# little2wire.net
KiCad netlist of a schematic drawn in EAGLE
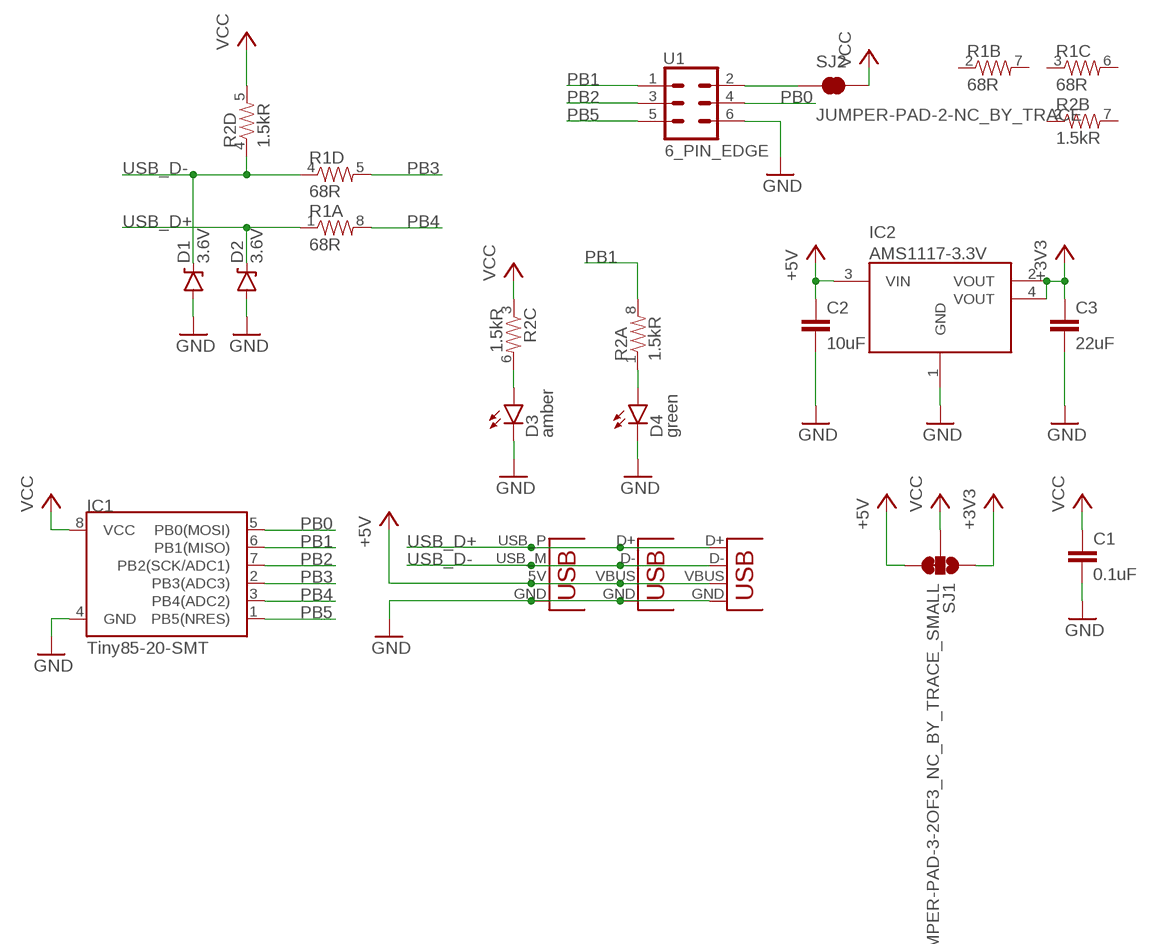
[diagram p0: schematic, sheet 1]

(export (version "E")
  (design (tool "Eeschema 10.0.6"))
  (components
    (comp (ref "C1")
      (value "0.1uF")
      (footprint "eagle-import:0805")
      (libsource (lib "eagle-import") (part "CAPACITOR0805"))
    )
    (comp (ref "C2")
      (value "10uF")
      (footprint "eagle-import:0805")
      (libsource (lib "eagle-import") (part "CAPACITOR0805"))
    )
    (comp (ref "C3")
      (value "22uF")
      (footprint "eagle-import:0805")
      (libsource (lib "eagle-import") (part "CAPACITOR0805"))
    )
    (comp (ref "D1")
      (value "3.6V")
      (footprint "eagle-import:SOD-323")
      (libsource (lib "eagle-import") (part "DIODE-ZENER_SOD323"))
    )
    (comp (ref "D2")
      (value "3.6V")
      (footprint "eagle-import:SOD-323")
      (libsource (lib "eagle-import") (part "DIODE-ZENER_SOD323"))
    )
    (comp (ref "D3")
      (value "amber")
      (footprint "eagle-import:LED-805")
      (libsource (lib "eagle-import") (part "LED805"))
    )
    (comp (ref "D4")
      (value "green")
      (footprint "eagle-import:LED-805")
      (libsource (lib "eagle-import") (part "LED805"))
    )
    (comp (ref "IC1")
      (value "Tiny85-20-SMT")
      (footprint "eagle-import:SO08-EIAJ")
      (libsource (lib "eagle-import") (part "ATTINY45TINY85-20-SMT"))
    )
    (comp (ref "IC2")
      (value "AMS1117-3.3V")
      (footprint "eagle-import:SOT223")
      (libsource (lib "eagle-import") (part "AMS1117_SOT223"))
    )
    (comp (ref "JP1")
      (value "USBPCB")
      (footprint "eagle-import:USB-A-PCB")
      (libsource (lib "eagle-import") (part "USBPCB"))
    )
    (comp (ref "JP2")
      (value "USBSMD")
      (footprint "eagle-import:USB-MINIB")
      (libsource (lib "eagle-import") (part "USBSMD"))
    )
    (comp (ref "JP3")
      (value "USB-MICROB")
      (footprint "eagle-import:USB-MICROB")
      (libsource (lib "eagle-import") (part "USB-MICROB"))
    )
    (comp (ref "R1")
      (value "68R")
      (footprint "eagle-import:1206-ARRAY")
      (libsource (lib "eagle-import") (part "RESISTOR-ARRAY1206ARR"))
    )
    (comp (ref "R2")
      (value "1.5kR")
      (footprint "eagle-import:1206-ARRAY")
      (libsource (lib "eagle-import") (part "RESISTOR-ARRAY1206ARR"))
    )
    (comp (ref "SJ1")
      (value "JUMPER-PAD-3-2OF3_NC_BY_TRACE_SMALL")
      (footprint "eagle-import:PAD-JUMPER-3-2OF3_NC_BY_TRACE_YES_SILK_FULL_BOX")
      (libsource (lib "eagle-import") (part "JUMPER-PAD-3-2OF3_NC_BY_TRACE_SMALL"))
    )
    (comp (ref "SJ2")
      (value "JUMPER-PAD-2-NC_BY_TRACE")
      (footprint "eagle-import:PAD-JUMPER-2-NC_BY_TRACE_YES_SILK")
      (libsource (lib "eagle-import") (part "JUMPER-PAD-2-NC_BY_TRACE"))
    )
    (comp (ref "U1")
      (value "6_PIN_EDGE")
      (footprint "eagle-import:6_PIN_EDGE")
      (libsource (lib "eagle-import") (part "6_PIN_EDGE"))
    )
  )
  (nets
    (net (code "1") (name "+3V3") (class "Default")
      (node (ref "C3") (pin "1") (pinfunction "1_1") (pintype "passive"))
      (node (ref "IC2") (pin "2") (pinfunction "VOUT_2") (pintype "bidirectional"))
      (node (ref "IC2") (pin "4") (pinfunction "VOUT_4") (pintype "bidirectional"))
      (node (ref "SJ1") (pin "1") (pinfunction "1_1") (pintype "passive"))
    )
    (net (code "2") (name "+5V") (class "Default")
      (node (ref "C2") (pin "1") (pinfunction "1_1") (pintype "passive"))
      (node (ref "IC2") (pin "3") (pinfunction "VIN_3") (pintype "bidirectional"))
      (node (ref "JP1") (pin "5V") (pinfunction "VBUS_5V") (pintype "bidirectional"))
      (node (ref "JP2") (pin "VBUS") (pinfunction "VBUS_VBUS") (pintype "bidirectional"))
      (node (ref "JP3") (pin "VBUS") (pinfunction "VBUS_VBUS") (pintype "bidirectional"))
      (node (ref "SJ1") (pin "3") (pinfunction "3_3") (pintype "passive"))
    )
    (net (code "3") (name "/PB0") (class "Default")
      (node (ref "IC1") (pin "5") (pinfunction "PB0(MOSI)_5") (pintype "bidirectional"))
      (node (ref "U1") (pin "4") (pinfunction "4_4") (pintype "passive"))
    )
    (net (code "4") (name "/PB1") (class "Default")
      (node (ref "IC1") (pin "6") (pinfunction "PB1(MISO)_6") (pintype "bidirectional"))
      (node (ref "R2") (pin "8") (pinfunction "2_8") (pintype "passive"))
      (node (ref "U1") (pin "1") (pinfunction "1_1") (pintype "passive"))
    )
    (net (code "5") (name "/PB2") (class "Default")
      (node (ref "IC1") (pin "7") (pinfunction "PB2(SCK/ADC1)_7") (pintype "bidirectional"))
      (node (ref "U1") (pin "3") (pinfunction "3_3") (pintype "passive"))
    )
    (net (code "6") (name "/PB3") (class "Default")
      (node (ref "IC1") (pin "2") (pinfunction "PB3(ADC3)_2") (pintype "bidirectional"))
      (node (ref "R1") (pin "5") (pinfunction "2_5") (pintype "passive"))
    )
    (net (code "7") (name "/PB4") (class "Default")
      (node (ref "IC1") (pin "3") (pinfunction "PB4(ADC2)_3") (pintype "bidirectional"))
      (node (ref "R1") (pin "8") (pinfunction "2_8") (pintype "passive"))
    )
    (net (code "8") (name "/PB5") (class "Default")
      (node (ref "IC1") (pin "1") (pinfunction "PB5(NRES)_1") (pintype "bidirectional"))
      (node (ref "U1") (pin "5") (pinfunction "5_5") (pintype "passive"))
    )
    (net (code "9") (name "/USB_D+") (class "Default")
      (node (ref "D2") (pin "C") (pinfunction "C_C") (pintype "passive"))
      (node (ref "JP1") (pin "USB_P") (pinfunction "D+_USB_P") (pintype "bidirectional"))
      (node (ref "JP2") (pin "D+") (pinfunction "D+_D+") (pintype "bidirectional"))
      (node (ref "JP3") (pin "D+") (pinfunction "D+_D+") (pintype "bidirectional"))
      (node (ref "R1") (pin "1") (pinfunction "1_1") (pintype "passive"))
    )
    (net (code "10") (name "/USB_D-") (class "Default")
      (node (ref "D1") (pin "C") (pinfunction "C_C") (pintype "passive"))
      (node (ref "JP1") (pin "USB_M") (pinfunction "D-_USB_M") (pintype "bidirectional"))
      (node (ref "JP2") (pin "D-") (pinfunction "D-_D-") (pintype "bidirectional"))
      (node (ref "JP3") (pin "D-") (pinfunction "D-_D-") (pintype "bidirectional"))
      (node (ref "R1") (pin "4") (pinfunction "1_4") (pintype "passive"))
      (node (ref "R2") (pin "4") (pinfunction "1_4") (pintype "passive"))
    )
    (net (code "11") (name "GND") (class "Default")
      (node (ref "C1") (pin "2") (pinfunction "2_2") (pintype "passive"))
      (node (ref "C2") (pin "2") (pinfunction "2_2") (pintype "passive"))
      (node (ref "C3") (pin "2") (pinfunction "2_2") (pintype "passive"))
      (node (ref "D1") (pin "A") (pinfunction "A_A") (pintype "passive"))
      (node (ref "D2") (pin "A") (pinfunction "A_A") (pintype "passive"))
      (node (ref "D3") (pin "C") (pinfunction "C_C") (pintype "passive"))
      (node (ref "D4") (pin "C") (pinfunction "C_C") (pintype "passive"))
      (node (ref "IC1") (pin "4") (pinfunction "GND_4") (pintype "bidirectional"))
      (node (ref "IC2") (pin "1") (pinfunction "GND_1") (pintype "bidirectional"))
      (node (ref "JP1") (pin "GND") (pinfunction "GND_GND") (pintype "bidirectional"))
      (node (ref "JP2") (pin "GND") (pinfunction "GND_GND") (pintype "bidirectional"))
      (node (ref "JP3") (pin "GND") (pinfunction "GND_GND") (pintype "bidirectional"))
      (node (ref "U1") (pin "6") (pinfunction "6_6") (pintype "passive"))
    )
    (net (code "12") (name "Net-(D4-PadA)") (class "Default")
      (node (ref "D4") (pin "A") (pinfunction "A_A") (pintype "passive"))
      (node (ref "R2") (pin "1") (pinfunction "1_1") (pintype "passive"))
    )
    (net (code "13") (name "Net-(R2C-2)") (class "Default")
      (node (ref "D3") (pin "A") (pinfunction "A_A") (pintype "passive"))
      (node (ref "R2") (pin "6") (pinfunction "2_6") (pintype "passive"))
    )
    (net (code "14") (name "Net-(SJ2-Pad1)") (class "Default")
      (node (ref "SJ2") (pin "1") (pinfunction "1_1") (pintype "passive"))
      (node (ref "U1") (pin "2") (pinfunction "2_2") (pintype "passive"))
    )
    (net (code "15") (name "VCC") (class "Default")
      (node (ref "C1") (pin "1") (pinfunction "1_1") (pintype "passive"))
      (node (ref "IC1") (pin "8") (pinfunction "VCC_8") (pintype "bidirectional"))
      (node (ref "R2") (pin "3") (pinfunction "1_3") (pintype "passive"))
      (node (ref "R2") (pin "5") (pinfunction "2_5") (pintype "passive"))
      (node (ref "SJ1") (pin "2") (pinfunction "2_2") (pintype "passive"))
      (node (ref "SJ2") (pin "2") (pinfunction "2_2") (pintype "passive"))
    )
    (net (code "16") (name "unconnected-(R1B-1-Pad2)") (class "Default")
      (node (ref "R1") (pin "2") (pinfunction "1_2") (pintype "passive"))
    )
    (net (code "17") (name "unconnected-(R1B-2-Pad7)") (class "Default")
      (node (ref "R1") (pin "7") (pinfunction "2_7") (pintype "passive"))
    )
    (net (code "18") (name "unconnected-(R1C-1-Pad3)") (class "Default")
      (node (ref "R1") (pin "3") (pinfunction "1_3") (pintype "passive"))
    )
    (net (code "19") (name "unconnected-(R1C-2-Pad6)") (class "Default")
      (node (ref "R1") (pin "6") (pinfunction "2_6") (pintype "passive"))
    )
    (net (code "20") (name "unconnected-(R2B-1-Pad2)") (class "Default")
      (node (ref "R2") (pin "2") (pinfunction "1_2") (pintype "passive"))
    )
    (net (code "21") (name "unconnected-(R2B-2-Pad7)") (class "Default")
      (node (ref "R2") (pin "7") (pinfunction "2_7") (pintype "passive"))
    )
  )
)
